# FuckIO_REV01.net
KiCad netlist of a schematic drawn in EAGLE
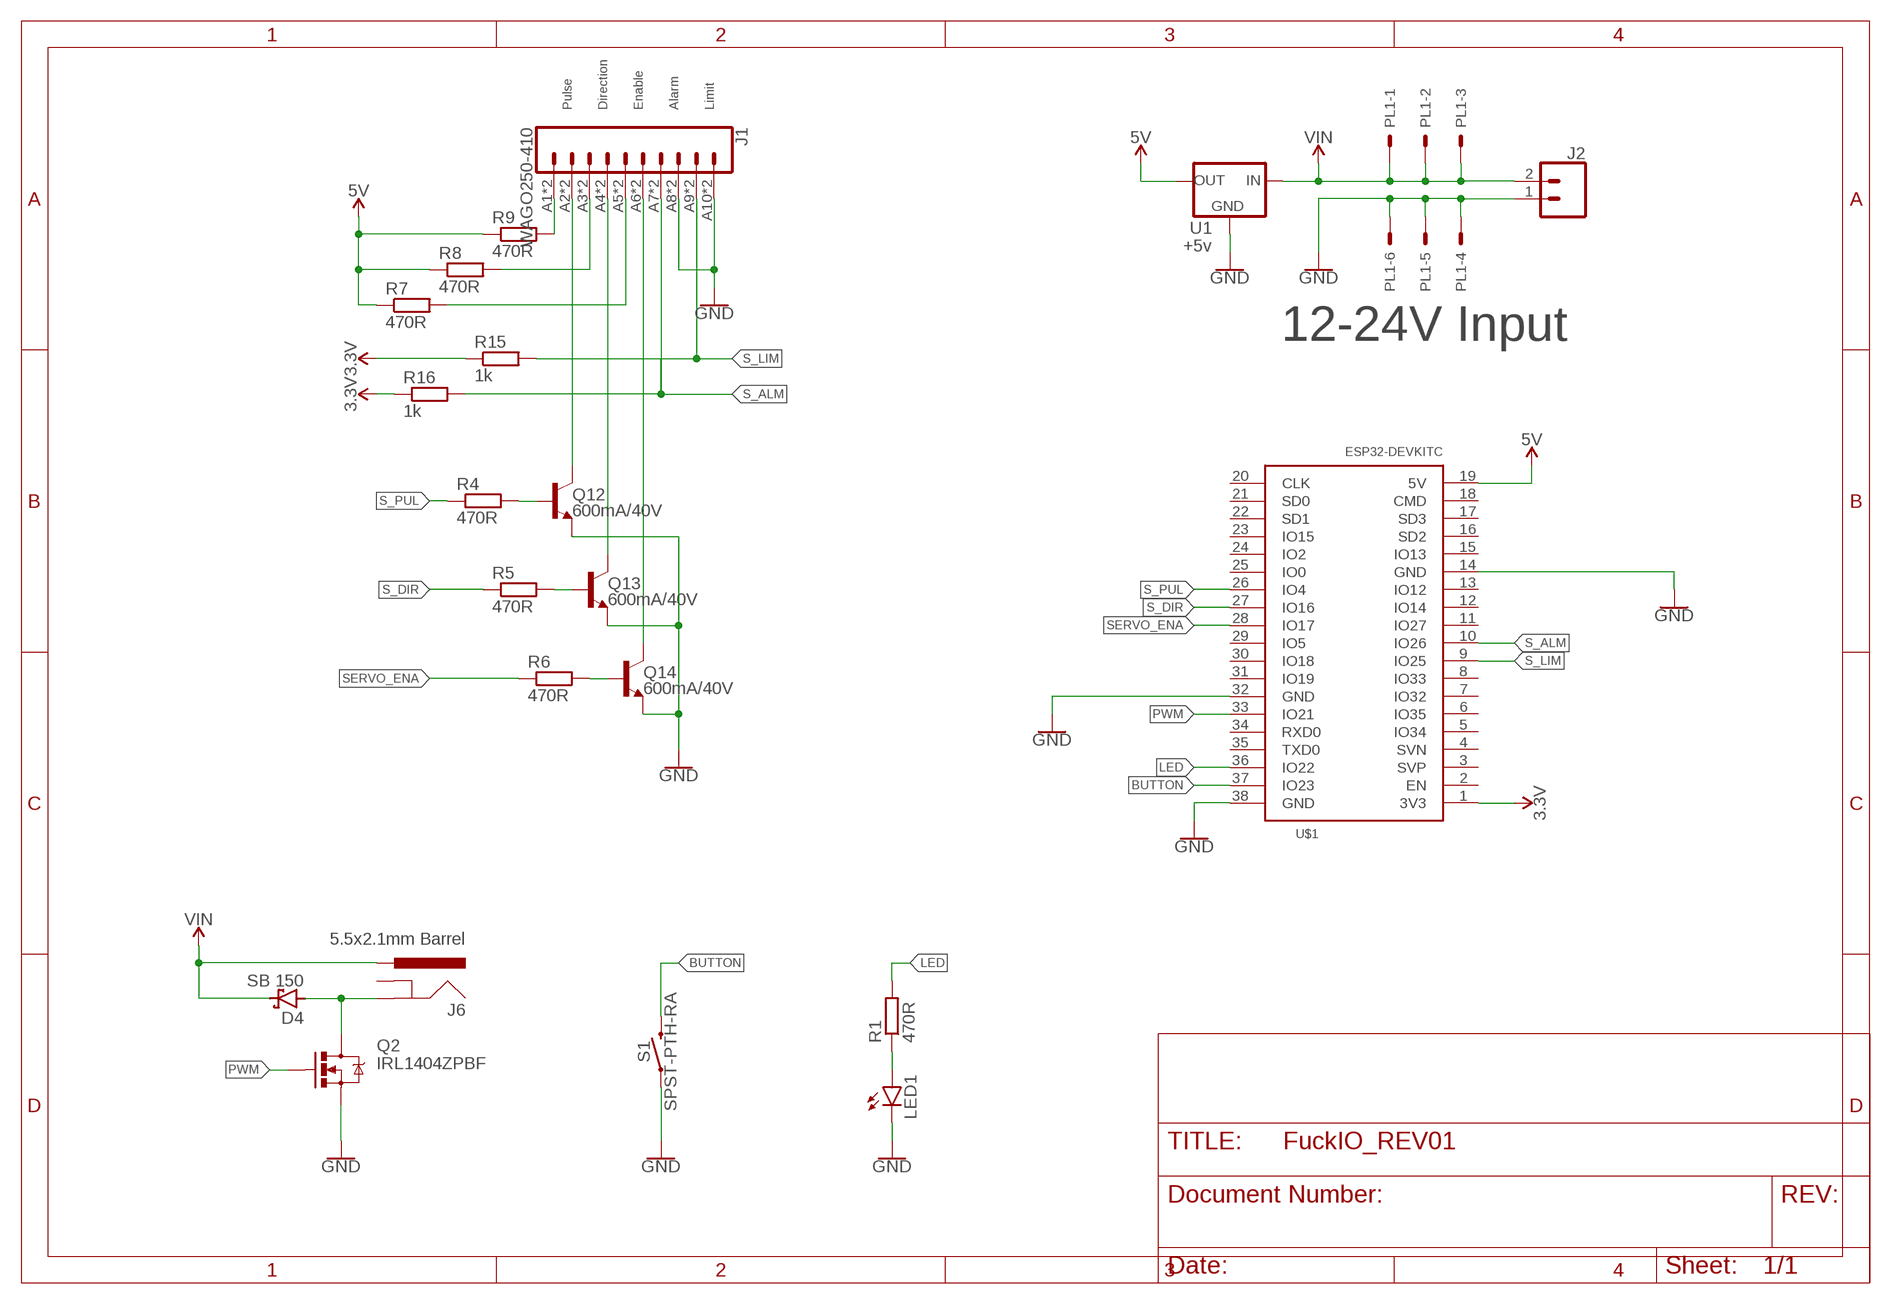
[diagram p0: schematic, sheet 1]

(export (version "E")
  (design (tool "Eeschema 10.0.6"))
  (components
    (comp (ref "D4")
      (value "SB 150")
      (footprint "eagle-import:DIODE_DO41-10")
      (libsource (lib "eagle-import") (part "BAT49"))
    )
    (comp (ref "J1")
      (value "WAGO250-410")
      (footprint "eagle-import:BEE_WAGO250-410")
      (libsource (lib "eagle-import") (part "WAGO250-410"))
    )
    (comp (ref "J2")
      (value "CONN_025MM")
      (footprint "eagle-import:SPARKFUN-CONNECTORS_SCREWTERMINAL-5MM-2")
      (libsource (lib "eagle-import") (part "CONN_025MM"))
    )
    (comp (ref "J6")
      (value "5.5x2.1mm Barrel")
      (footprint "eagle-import:SPARKFUN-CONNECTORS_POWER_JACK_PTH")
      (libsource (lib "eagle-import") (part "POWER_JACK"))
    )
    (comp (ref "LED1")
      (value "LED5MM")
      (footprint "eagle-import:LED5MM")
      (libsource (lib "eagle-import") (part "LED5MM"))
    )
    (comp (ref "PL1")
      (value "CON-MOLEX-2_555X-6H")
      (footprint "eagle-import:CON-MOLEX-2_5569-6")
      (libsource (lib "eagle-import") (part "CON-MOLEX-2_555X-6H"))
    )
    (comp (ref "Q2")
      (value "IRL1404ZPBF")
      (footprint "eagle-import:BEE_TO220-IGO")
      (libsource (lib "eagle-import") (part "MOSFET-NCHANNELTO220"))
    )
    (comp (ref "Q12")
      (value "600mA/40V")
      (footprint "eagle-import:SPARKFUN-DISCRETESEMI_TO-92")
      (libsource (lib "eagle-import") (part "TRANS_NPN-P2N2222A"))
    )
    (comp (ref "Q13")
      (value "600mA/40V")
      (footprint "eagle-import:SPARKFUN-DISCRETESEMI_TO-92")
      (libsource (lib "eagle-import") (part "TRANS_NPN-P2N2222A"))
    )
    (comp (ref "Q14")
      (value "600mA/40V")
      (footprint "eagle-import:SPARKFUN-DISCRETESEMI_TO-92")
      (libsource (lib "eagle-import") (part "TRANS_NPN-P2N2222A"))
    )
    (comp (ref "R1")
      (value "470R")
      (footprint "eagle-import:RCL_0204_5")
      (libsource (lib "eagle-import") (part "RCL_R-EU_0204/5"))
    )
    (comp (ref "R4")
      (value "470R")
      (footprint "eagle-import:RCL_0204_5")
      (libsource (lib "eagle-import") (part "RCL_R-EU_0204/5"))
    )
    (comp (ref "R5")
      (value "470R")
      (footprint "eagle-import:RCL_0204_5")
      (libsource (lib "eagle-import") (part "RCL_R-EU_0204/5"))
    )
    (comp (ref "R6")
      (value "470R")
      (footprint "eagle-import:RCL_0204_5")
      (libsource (lib "eagle-import") (part "RCL_R-EU_0204/5"))
    )
    (comp (ref "R7")
      (value "470R")
      (footprint "eagle-import:RCL_0204_5")
      (libsource (lib "eagle-import") (part "RCL_R-EU_0204/5"))
    )
    (comp (ref "R8")
      (value "470R")
      (footprint "eagle-import:RCL_0204_5")
      (libsource (lib "eagle-import") (part "RCL_R-EU_0204/5"))
    )
    (comp (ref "R9")
      (value "470R")
      (footprint "eagle-import:RCL_0204_5")
      (libsource (lib "eagle-import") (part "RCL_R-EU_0204/5"))
    )
    (comp (ref "R15")
      (value "1k")
      (footprint "eagle-import:RCL_0204_5")
      (libsource (lib "eagle-import") (part "RCL_R-EU_0204/5"))
    )
    (comp (ref "R16")
      (value "1k")
      (footprint "eagle-import:RCL_0204_5")
      (libsource (lib "eagle-import") (part "RCL_R-EU_0204/5"))
    )
    (comp (ref "S1")
      (value "SPST-PTH-RA")
      (footprint "eagle-import:TACTILE_SWITCH_PTH_RIGHT_ANGLE_KIT")
      (libsource (lib "eagle-import") (part "MOMENTARY-SWITCH-SPST-PTH-RIGHT-ANGLE-KIT"))
    )
    (comp (ref "U$1")
      (value "ESP32DEVKITC")
      (footprint "eagle-import:ESP32-DEVKITC")
      (libsource (lib "eagle-import") (part "ESP32DEVKITC"))
    )
    (comp (ref "U1")
      (value "+5v")
      (footprint "eagle-import:SPARKFUN-IC-POWER_TO220-IGO")
      (libsource (lib "eagle-import") (part "V_REG_78XXSINK"))
    )
  )
  (nets
    (net (code "1") (name "3.3V") (class "Default")
      (node (ref "R15") (pin "1") (pinfunction "1_1") (pintype "passive"))
      (node (ref "R16") (pin "1") (pinfunction "1_1") (pintype "passive"))
      (node (ref "U$1") (pin "1") (pinfunction "3V3_1") (pintype "bidirectional"))
    )
    (net (code "2") (name "5V") (class "Default")
      (node (ref "R7") (pin "1") (pinfunction "1_1") (pintype "passive"))
      (node (ref "R8") (pin "1") (pinfunction "1_1") (pintype "passive"))
      (node (ref "R9") (pin "1") (pinfunction "1_1") (pintype "passive"))
      (node (ref "U$1") (pin "19") (pinfunction "5V_19") (pintype "bidirectional"))
      (node (ref "U1") (pin "OUT") (pinfunction "OUT_OUT") (pintype "passive"))
    )
    (net (code "3") (name "BUTTON") (class "Default")
      (node (ref "S1") (pin "2") (pinfunction "2_2") (pintype "passive"))
      (node (ref "U$1") (pin "37") (pinfunction "IO23_37") (pintype "bidirectional"))
    )
    (net (code "4") (name "GND") (class "Default")
      (node (ref "J1") (pin "A10") (pinfunction "10_A10") (pintype "passive"))
      (node (ref "J1") (pin "A8") (pinfunction "8_A8") (pintype "passive"))
      (node (ref "J1") (pin "B10") (pinfunction "10_B10") (pintype "passive"))
      (node (ref "J1") (pin "B8") (pinfunction "8_B8") (pintype "passive"))
      (node (ref "J2") (pin "1") (pinfunction "1_1") (pintype "passive"))
      (node (ref "LED1") (pin "K") (pinfunction "C_K") (pintype "passive"))
      (node (ref "PL1") (pin "4") (pinfunction "S_4") (pintype "passive"))
      (node (ref "PL1") (pin "5") (pinfunction "S_5") (pintype "passive"))
      (node (ref "PL1") (pin "6") (pinfunction "S_6") (pintype "passive"))
      (node (ref "Q12") (pin "3") (pinfunction "E_3") (pintype "passive"))
      (node (ref "Q13") (pin "3") (pinfunction "E_3") (pintype "passive"))
      (node (ref "Q14") (pin "3") (pinfunction "E_3") (pintype "passive"))
      (node (ref "Q2") (pin "S") (pinfunction "S_S") (pintype "passive"))
      (node (ref "S1") (pin "1") (pinfunction "1_1") (pintype "passive"))
      (node (ref "U$1") (pin "14") (pinfunction "GND_14") (pintype "bidirectional"))
      (node (ref "U$1") (pin "32") (pinfunction "GND_32") (pintype "bidirectional"))
      (node (ref "U$1") (pin "38") (pinfunction "GND_38") (pintype "bidirectional"))
      (node (ref "U1") (pin "GND") (pinfunction "GND_GND") (pintype "input"))
    )
    (net (code "5") (name "LED") (class "Default")
      (node (ref "R1") (pin "2") (pinfunction "2_2") (pintype "passive"))
      (node (ref "U$1") (pin "36") (pinfunction "IO22_36") (pintype "bidirectional"))
    )
    (net (code "6") (name "Net-(D4-PadA)") (class "Default")
      (node (ref "D4") (pin "A") (pinfunction "A_A") (pintype "passive"))
      (node (ref "J6") (pin "GND") (pinfunction "GND_GND") (pintype "bidirectional"))
      (node (ref "Q2") (pin "D") (pinfunction "D_D") (pintype "passive"))
    )
    (net (code "7") (name "Net-(J1-1-PadA1)") (class "Default")
      (node (ref "J1") (pin "A1") (pinfunction "1_A1") (pintype "passive"))
      (node (ref "J1") (pin "B1") (pinfunction "1_B1") (pintype "passive"))
      (node (ref "R9") (pin "2") (pinfunction "2_2") (pintype "passive"))
    )
    (net (code "8") (name "Net-(J1-3-PadA3)") (class "Default")
      (node (ref "J1") (pin "A3") (pinfunction "3_A3") (pintype "passive"))
      (node (ref "J1") (pin "B3") (pinfunction "3_B3") (pintype "passive"))
      (node (ref "R8") (pin "2") (pinfunction "2_2") (pintype "passive"))
    )
    (net (code "9") (name "Net-(J1-5-PadA5)") (class "Default")
      (node (ref "J1") (pin "A5") (pinfunction "5_A5") (pintype "passive"))
      (node (ref "J1") (pin "B5") (pinfunction "5_B5") (pintype "passive"))
      (node (ref "R7") (pin "2") (pinfunction "2_2") (pintype "passive"))
    )
    (net (code "10") (name "Net-(LED1-PadA)") (class "Default")
      (node (ref "LED1") (pin "A") (pinfunction "A_A") (pintype "passive"))
      (node (ref "R1") (pin "1") (pinfunction "1_1") (pintype "passive"))
    )
    (net (code "11") (name "Net-(Q12-B)") (class "Default")
      (node (ref "Q12") (pin "2") (pinfunction "B_2") (pintype "passive"))
      (node (ref "R4") (pin "2") (pinfunction "2_2") (pintype "passive"))
    )
    (net (code "12") (name "Net-(Q12-C)") (class "Default")
      (node (ref "J1") (pin "A2") (pinfunction "2_A2") (pintype "passive"))
      (node (ref "J1") (pin "B2") (pinfunction "2_B2") (pintype "passive"))
      (node (ref "Q12") (pin "1") (pinfunction "C_1") (pintype "passive"))
    )
    (net (code "13") (name "Net-(Q13-B)") (class "Default")
      (node (ref "Q13") (pin "2") (pinfunction "B_2") (pintype "passive"))
      (node (ref "R5") (pin "2") (pinfunction "2_2") (pintype "passive"))
    )
    (net (code "14") (name "Net-(Q13-C)") (class "Default")
      (node (ref "J1") (pin "A4") (pinfunction "4_A4") (pintype "passive"))
      (node (ref "J1") (pin "B4") (pinfunction "4_B4") (pintype "passive"))
      (node (ref "Q13") (pin "1") (pinfunction "C_1") (pintype "passive"))
    )
    (net (code "15") (name "Net-(Q14-B)") (class "Default")
      (node (ref "Q14") (pin "2") (pinfunction "B_2") (pintype "passive"))
      (node (ref "R6") (pin "2") (pinfunction "2_2") (pintype "passive"))
    )
    (net (code "16") (name "Net-(Q14-C)") (class "Default")
      (node (ref "J1") (pin "A6") (pinfunction "6_A6") (pintype "passive"))
      (node (ref "J1") (pin "B6") (pinfunction "6_B6") (pintype "passive"))
      (node (ref "Q14") (pin "1") (pinfunction "C_1") (pintype "passive"))
    )
    (net (code "17") (name "PWM") (class "Default")
      (node (ref "Q2") (pin "G") (pinfunction "G_G") (pintype "passive"))
      (node (ref "U$1") (pin "33") (pinfunction "IO21_33") (pintype "bidirectional"))
    )
    (net (code "18") (name "SERVO_ENA") (class "Default")
      (node (ref "R6") (pin "1") (pinfunction "1_1") (pintype "passive"))
      (node (ref "U$1") (pin "28") (pinfunction "IO17_28") (pintype "bidirectional"))
    )
    (net (code "19") (name "S_ALM") (class "Default")
      (node (ref "J1") (pin "A7") (pinfunction "7_A7") (pintype "passive"))
      (node (ref "J1") (pin "B7") (pinfunction "7_B7") (pintype "passive"))
      (node (ref "R16") (pin "2") (pinfunction "2_2") (pintype "passive"))
      (node (ref "U$1") (pin "10") (pinfunction "IO26_10") (pintype "bidirectional"))
    )
    (net (code "20") (name "S_DIR") (class "Default")
      (node (ref "R5") (pin "1") (pinfunction "1_1") (pintype "passive"))
      (node (ref "U$1") (pin "27") (pinfunction "IO16_27") (pintype "bidirectional"))
    )
    (net (code "21") (name "S_LIM") (class "Default")
      (node (ref "J1") (pin "A9") (pinfunction "9_A9") (pintype "passive"))
      (node (ref "J1") (pin "B9") (pinfunction "9_B9") (pintype "passive"))
      (node (ref "R15") (pin "2") (pinfunction "2_2") (pintype "passive"))
      (node (ref "U$1") (pin "9") (pinfunction "IO25_9") (pintype "bidirectional"))
    )
    (net (code "22") (name "S_PUL") (class "Default")
      (node (ref "R4") (pin "1") (pinfunction "1_1") (pintype "passive"))
      (node (ref "U$1") (pin "26") (pinfunction "IO4_26") (pintype "bidirectional"))
    )
    (net (code "23") (name "VIN") (class "Default")
      (node (ref "D4") (pin "C") (pinfunction "C_C") (pintype "passive"))
      (node (ref "J2") (pin "2") (pinfunction "2_2") (pintype "passive"))
      (node (ref "J6") (pin "PWR") (pinfunction "PWR_PWR") (pintype "bidirectional"))
      (node (ref "PL1") (pin "1") (pinfunction "S_1") (pintype "passive"))
      (node (ref "PL1") (pin "2") (pinfunction "S_2") (pintype "passive"))
      (node (ref "PL1") (pin "3") (pinfunction "S_3") (pintype "passive"))
      (node (ref "U1") (pin "IN") (pinfunction "IN_IN") (pintype "input"))
    )
    (net (code "24") (name "unconnected-(J6-PadGNDBREAK)") (class "Default")
      (node (ref "J6") (pin "GNDBREAK") (pinfunction "GNDBREAK_GNDBREAK") (pintype "bidirectional"))
    )
    (net (code "25") (name "unconnected-(U$1-CLK-Pad20)") (class "Default")
      (node (ref "U$1") (pin "20") (pinfunction "CLK_20") (pintype "bidirectional"))
    )
    (net (code "26") (name "unconnected-(U$1-CMD-Pad18)") (class "Default")
      (node (ref "U$1") (pin "18") (pinfunction "CMD_18") (pintype "bidirectional"))
    )
    (net (code "27") (name "unconnected-(U$1-EN-Pad2)") (class "Default")
      (node (ref "U$1") (pin "2") (pinfunction "EN_2") (pintype "bidirectional"))
    )
    (net (code "28") (name "unconnected-(U$1-IO0-Pad25)") (class "Default")
      (node (ref "U$1") (pin "25") (pinfunction "IO0_25") (pintype "bidirectional"))
    )
    (net (code "29") (name "unconnected-(U$1-IO2-Pad24)") (class "Default")
      (node (ref "U$1") (pin "24") (pinfunction "IO2_24") (pintype "bidirectional"))
    )
    (net (code "30") (name "unconnected-(U$1-IO5-Pad29)") (class "Default")
      (node (ref "U$1") (pin "29") (pinfunction "IO5_29") (pintype "bidirectional"))
    )
    (net (code "31") (name "unconnected-(U$1-IO12-Pad13)") (class "Default")
      (node (ref "U$1") (pin "13") (pinfunction "IO12_13") (pintype "bidirectional"))
    )
    (net (code "32") (name "unconnected-(U$1-IO13-Pad15)") (class "Default")
      (node (ref "U$1") (pin "15") (pinfunction "IO13_15") (pintype "bidirectional"))
    )
    (net (code "33") (name "unconnected-(U$1-IO14-Pad12)") (class "Default")
      (node (ref "U$1") (pin "12") (pinfunction "IO14_12") (pintype "bidirectional"))
    )
    (net (code "34") (name "unconnected-(U$1-IO15-Pad23)") (class "Default")
      (node (ref "U$1") (pin "23") (pinfunction "IO15_23") (pintype "bidirectional"))
    )
    (net (code "35") (name "unconnected-(U$1-IO18-Pad30)") (class "Default")
      (node (ref "U$1") (pin "30") (pinfunction "IO18_30") (pintype "bidirectional"))
    )
    (net (code "36") (name "unconnected-(U$1-IO19-Pad31)") (class "Default")
      (node (ref "U$1") (pin "31") (pinfunction "IO19_31") (pintype "bidirectional"))
    )
    (net (code "37") (name "unconnected-(U$1-IO27-Pad11)") (class "Default")
      (node (ref "U$1") (pin "11") (pinfunction "IO27_11") (pintype "bidirectional"))
    )
    (net (code "38") (name "unconnected-(U$1-IO32-Pad7)") (class "Default")
      (node (ref "U$1") (pin "7") (pinfunction "IO32_7") (pintype "bidirectional"))
    )
    (net (code "39") (name "unconnected-(U$1-IO33-Pad8)") (class "Default")
      (node (ref "U$1") (pin "8") (pinfunction "IO33_8") (pintype "bidirectional"))
    )
    (net (code "40") (name "unconnected-(U$1-IO34-Pad5)") (class "Default")
      (node (ref "U$1") (pin "5") (pinfunction "IO34_5") (pintype "bidirectional"))
    )
    (net (code "41") (name "unconnected-(U$1-IO35-Pad6)") (class "Default")
      (node (ref "U$1") (pin "6") (pinfunction "IO35_6") (pintype "bidirectional"))
    )
    (net (code "42") (name "unconnected-(U$1-RXD0-Pad34)") (class "Default")
      (node (ref "U$1") (pin "34") (pinfunction "RXD0_34") (pintype "bidirectional"))
    )
    (net (code "43") (name "unconnected-(U$1-SD0-Pad21)") (class "Default")
      (node (ref "U$1") (pin "21") (pinfunction "SD0_21") (pintype "bidirectional"))
    )
    (net (code "44") (name "unconnected-(U$1-SD1-Pad22)") (class "Default")
      (node (ref "U$1") (pin "22") (pinfunction "SD1_22") (pintype "bidirectional"))
    )
    (net (code "45") (name "unconnected-(U$1-SD2-Pad16)") (class "Default")
      (node (ref "U$1") (pin "16") (pinfunction "SD2_16") (pintype "bidirectional"))
    )
    (net (code "46") (name "unconnected-(U$1-SD3-Pad17)") (class "Default")
      (node (ref "U$1") (pin "17") (pinfunction "SD3_17") (pintype "bidirectional"))
    )
    (net (code "47") (name "unconnected-(U$1-SVN-Pad4)") (class "Default")
      (node (ref "U$1") (pin "4") (pinfunction "SVN_4") (pintype "bidirectional"))
    )
    (net (code "48") (name "unconnected-(U$1-SVP-Pad3)") (class "Default")
      (node (ref "U$1") (pin "3") (pinfunction "SVP_3") (pintype "bidirectional"))
    )
    (net (code "49") (name "unconnected-(U$1-TXD0-Pad35)") (class "Default")
      (node (ref "U$1") (pin "35") (pinfunction "TXD0_35") (pintype "bidirectional"))
    )
  )
)
